# Amp_op4.net
KiCad netlist of a schematic drawn in Altium Designer
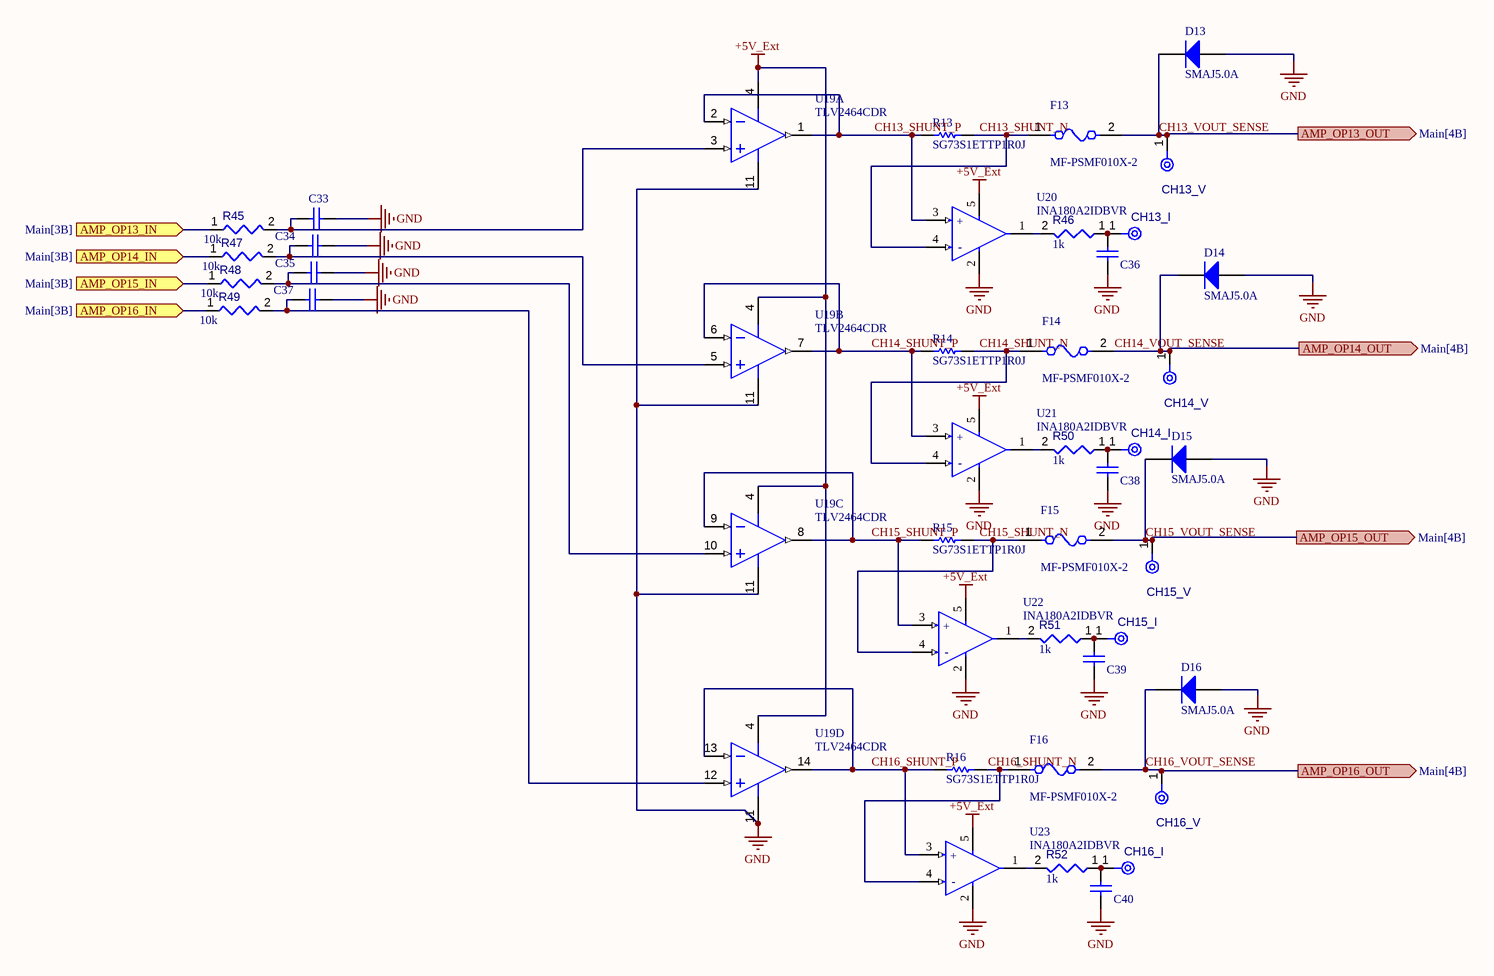
[diagram p0: Amp_op4.SchDoc]

(export (version "E")
  (design (tool "Eeschema 10.0.6"))
  (components
    (comp (ref "C33")
      (value "VJ0603Y104MXJCW1BC")
      (footprint "CAPC1608X95X40NL15T15")
      (fields (field (name "MANUFACTURER") "Vitramon"))
      (libsource (lib "Altium Content Vault") (part "CAP"))
    )
    (comp (ref "C34")
      (value "VJ0603Y104MXJCW1BC")
      (footprint "CAPC1608X95X40NL15T15")
      (fields (field (name "MANUFACTURER") "Vitramon"))
      (libsource (lib "Altium Content Vault") (part "CAP"))
    )
    (comp (ref "C35")
      (value "VJ0603Y104MXJCW1BC")
      (footprint "CAPC1608X95X40NL15T15")
      (fields (field (name "MANUFACTURER") "Vitramon"))
      (libsource (lib "Altium Content Vault") (part "CAP"))
    )
    (comp (ref "C36")
      (value "VJ0603Y104MXJCW1BC")
      (footprint "CAPC1608X95X40NL15T15")
      (fields (field (name "MANUFACTURER") "Vitramon"))
      (libsource (lib "Altium Content Vault") (part "CAP"))
    )
    (comp (ref "C37")
      (value "VJ0603Y104MXJCW1BC")
      (footprint "CAPC1608X95X40NL15T15")
      (fields (field (name "MANUFACTURER") "Vitramon"))
      (libsource (lib "Altium Content Vault") (part "CAP"))
    )
    (comp (ref "C38")
      (value "VJ0603Y104MXJCW1BC")
      (footprint "CAPC1608X95X40NL15T15")
      (fields (field (name "MANUFACTURER") "Vitramon"))
      (libsource (lib "Altium Content Vault") (part "CAP"))
    )
    (comp (ref "C39")
      (value "VJ0603Y104MXJCW1BC")
      (footprint "CAPC1608X95X40NL15T15")
      (fields (field (name "MANUFACTURER") "Vitramon"))
      (libsource (lib "Altium Content Vault") (part "CAP"))
    )
    (comp (ref "C40")
      (value "VJ0603Y104MXJCW1BC")
      (footprint "CAPC1608X95X40NL15T15")
      (fields (field (name "MANUFACTURER") "Vitramon"))
      (libsource (lib "Altium Content Vault") (part "CAP"))
    )
    (comp (ref "CH13_I")
      (value "TPAD6R")
      (footprint "TP06R")
      (description "0.6mm round")
      (libsource (lib "PCEIOT") (part "CMP-00028-00002-2"))
    )
    (comp (ref "CH13_V")
      (value "TPAD6R")
      (footprint "TP06R")
      (description "0.6mm round")
      (libsource (lib "PCEIOT") (part "CMP-00028-00002-2"))
    )
    (comp (ref "CH14_I")
      (value "TPAD6R")
      (footprint "TP06R")
      (description "0.6mm round")
      (libsource (lib "PCEIOT") (part "CMP-00028-00002-2"))
    )
    (comp (ref "CH14_V")
      (value "TPAD6R")
      (footprint "TP06R")
      (description "0.6mm round")
      (libsource (lib "PCEIOT") (part "CMP-00028-00002-2"))
    )
    (comp (ref "CH15_I")
      (value "TPAD6R")
      (footprint "TP06R")
      (description "0.6mm round")
      (libsource (lib "PCEIOT") (part "CMP-00028-00002-2"))
    )
    (comp (ref "CH15_V")
      (value "TPAD6R")
      (footprint "TP06R")
      (description "0.6mm round")
      (libsource (lib "PCEIOT") (part "CMP-00028-00002-2"))
    )
    (comp (ref "CH16_I")
      (value "TPAD6R")
      (footprint "TP06R")
      (description "0.6mm round")
      (libsource (lib "PCEIOT") (part "CMP-00028-00002-2"))
    )
    (comp (ref "CH16_V")
      (value "TPAD6R")
      (footprint "TP06R")
      (description "0.6mm round")
      (libsource (lib "PCEIOT") (part "CMP-00028-00002-2"))
    )
    (comp (ref "D13")
      (value "SMAJ5.0A")
      (footprint "BOUR-SMA-2_V")
      (fields (field (name "MANUFACTURER") "Bourns"))
      (libsource (lib "Altium Content Vault") (part "D-AK-2"))
    )
    (comp (ref "D14")
      (value "SMAJ5.0A")
      (footprint "BOUR-SMA-2_V")
      (fields (field (name "MANUFACTURER") "Bourns"))
      (libsource (lib "Altium Content Vault") (part "D-AK-2"))
    )
    (comp (ref "D15")
      (value "SMAJ5.0A")
      (footprint "BOUR-SMA-2_V")
      (fields (field (name "MANUFACTURER") "Bourns"))
      (libsource (lib "Altium Content Vault") (part "D-AK-2"))
    )
    (comp (ref "D16")
      (value "SMAJ5.0A")
      (footprint "BOUR-SMA-2_V")
      (fields (field (name "MANUFACTURER") "Bourns"))
      (libsource (lib "Altium Content Vault") (part "D-AK-2"))
    )
    (comp (ref "F13")
      (value "MF-PSMF010X-2")
      (footprint "FP-MF-PSMF-MFG")
      (description "PTC RESET FUSE 15V 100MA 0805")
      (fields
        (field (name "OCTOPART") "https://octopart.com/mf-psmf010x-2-bourns-7483441")
        (field (name "MANUFACTURER") "Bourns Inc.")
      )
      (libsource (lib "Altium Content Vault") (part "5bcf9b9f640e542cf0359d10258e979"))
    )
    (comp (ref "F14")
      (value "MF-PSMF010X-2")
      (footprint "FP-MF-PSMF-MFG")
      (description "PTC RESET FUSE 15V 100MA 0805")
      (fields
        (field (name "OCTOPART") "https://octopart.com/mf-psmf010x-2-bourns-7483441")
        (field (name "MANUFACTURER") "Bourns Inc.")
      )
      (libsource (lib "Altium Content Vault") (part "5bcf9b9f640e542cf0359d10258e979"))
    )
    (comp (ref "F15")
      (value "MF-PSMF010X-2")
      (footprint "FP-MF-PSMF-MFG")
      (description "PTC RESET FUSE 15V 100MA 0805")
      (fields
        (field (name "OCTOPART") "https://octopart.com/mf-psmf010x-2-bourns-7483441")
        (field (name "MANUFACTURER") "Bourns Inc.")
      )
      (libsource (lib "Altium Content Vault") (part "5bcf9b9f640e542cf0359d10258e979"))
    )
    (comp (ref "F16")
      (value "MF-PSMF010X-2")
      (footprint "FP-MF-PSMF-MFG")
      (description "PTC RESET FUSE 15V 100MA 0805")
      (fields
        (field (name "OCTOPART") "https://octopart.com/mf-psmf010x-2-bourns-7483441")
        (field (name "MANUFACTURER") "Bourns Inc.")
      )
      (libsource (lib "Altium Content Vault") (part "5bcf9b9f640e542cf0359d10258e979"))
    )
    (comp (ref "R13")
      (value "SG73S1ETTP1R0J")
      (footprint "RESC1005X40X25LL10T10")
      (fields (field (name "MANUFACTURER") "KOA Speer"))
      (libsource (lib "Altium Content Vault") (part "RES"))
    )
    (comp (ref "R14")
      (value "SG73S1ETTP1R0J")
      (footprint "RESC1005X40X25LL10T10")
      (fields (field (name "MANUFACTURER") "KOA Speer"))
      (libsource (lib "Altium Content Vault") (part "RES"))
    )
    (comp (ref "R15")
      (value "SG73S1ETTP1R0J")
      (footprint "RESC1005X40X25LL10T10")
      (fields (field (name "MANUFACTURER") "KOA Speer"))
      (libsource (lib "Altium Content Vault") (part "RES"))
    )
    (comp (ref "R16")
      (value "SG73S1ETTP1R0J")
      (footprint "RESC1005X40X25LL10T10")
      (fields (field (name "MANUFACTURER") "KOA Speer"))
      (libsource (lib "Altium Content Vault") (part "RES"))
    )
    (comp (ref "R45")
      (value "10k")
      (footprint "RESC0603(1608)_L")
      (description "Chip Resistor, 10 KOhm, +/- 1%, 01 W, -55 to 155 degC, 0603 (1608 Metric)")
      (fields (field (name "POWER") "100mW") (field (name "TOLERANCE") "1%"))
      (libsource (lib "PCEIOT") (part "CMP-009-00017-7"))
    )
    (comp (ref "R46")
      (value "1k")
      (footprint "RESC0603(1608)_L")
      (description "Chip Resistor, 1 KOhm, +/-1%, 0.1 W, -55 to 155 degC, 0603 (1608 Metric)")
      (fields (field (name "POWER") "100mW") (field (name "TOLERANCE") "1%"))
      (libsource (lib "PCEIOT") (part "CMP-009-00014-6"))
    )
    (comp (ref "R47")
      (value "10k")
      (footprint "RESC0603(1608)_L")
      (description "Chip Resistor, 10 KOhm, +/- 1%, 01 W, -55 to 155 degC, 0603 (1608 Metric)")
      (fields (field (name "POWER") "100mW") (field (name "TOLERANCE") "1%"))
      (libsource (lib "PCEIOT") (part "CMP-009-00017-7"))
    )
    (comp (ref "R48")
      (value "10k")
      (footprint "RESC0603(1608)_L")
      (description "Chip Resistor, 10 KOhm, +/- 1%, 01 W, -55 to 155 degC, 0603 (1608 Metric)")
      (fields (field (name "POWER") "100mW") (field (name "TOLERANCE") "1%"))
      (libsource (lib "PCEIOT") (part "CMP-009-00017-7"))
    )
    (comp (ref "R49")
      (value "10k")
      (footprint "RESC0603(1608)_L")
      (description "Chip Resistor, 10 KOhm, +/- 1%, 01 W, -55 to 155 degC, 0603 (1608 Metric)")
      (fields (field (name "POWER") "100mW") (field (name "TOLERANCE") "1%"))
      (libsource (lib "PCEIOT") (part "CMP-009-00017-7"))
    )
    (comp (ref "R50")
      (value "1k")
      (footprint "RESC0603(1608)_L")
      (description "Chip Resistor, 1 KOhm, +/-1%, 0.1 W, -55 to 155 degC, 0603 (1608 Metric)")
      (fields (field (name "POWER") "100mW") (field (name "TOLERANCE") "1%"))
      (libsource (lib "PCEIOT") (part "CMP-009-00014-6"))
    )
    (comp (ref "R51")
      (value "1k")
      (footprint "RESC0603(1608)_L")
      (description "Chip Resistor, 1 KOhm, +/-1%, 0.1 W, -55 to 155 degC, 0603 (1608 Metric)")
      (fields (field (name "POWER") "100mW") (field (name "TOLERANCE") "1%"))
      (libsource (lib "PCEIOT") (part "CMP-009-00014-6"))
    )
    (comp (ref "R52")
      (value "1k")
      (footprint "RESC0603(1608)_L")
      (description "Chip Resistor, 1 KOhm, +/-1%, 0.1 W, -55 to 155 degC, 0603 (1608 Metric)")
      (fields (field (name "POWER") "100mW") (field (name "TOLERANCE") "1%"))
      (libsource (lib "PCEIOT") (part "CMP-009-00014-6"))
    )
    (comp (ref "U19")
      (value "TLV2464CDR")
      (footprint "D0014A_N")
      (fields (field (name "MANUFACTURER") "Texas Instruments"))
      (libsource (lib "Altium Content Vault") (part "TI-TLV2464X-XX14"))
    )
    (comp (ref "U20")
      (value "INA180A2IDBVR")
      (footprint "FP-DBV0005A-MFG")
      (description "IC CURR SENSE 1 CIRCUIT SOT23-5")
      (libsource (lib "Altium Content Vault") (part "0a55cf1a948ad01a3239aec1b7efad0"))
    )
    (comp (ref "U21")
      (value "INA180A2IDBVR")
      (footprint "FP-DBV0005A-MFG")
      (description "IC CURR SENSE 1 CIRCUIT SOT23-5")
      (libsource (lib "Altium Content Vault") (part "0a55cf1a948ad01a3239aec1b7efad0"))
    )
    (comp (ref "U22")
      (value "INA180A2IDBVR")
      (footprint "FP-DBV0005A-MFG")
      (description "IC CURR SENSE 1 CIRCUIT SOT23-5")
      (libsource (lib "Altium Content Vault") (part "0a55cf1a948ad01a3239aec1b7efad0"))
    )
    (comp (ref "U23")
      (value "INA180A2IDBVR")
      (footprint "FP-DBV0005A-MFG")
      (description "IC CURR SENSE 1 CIRCUIT SOT23-5")
      (libsource (lib "Altium Content Vault") (part "0a55cf1a948ad01a3239aec1b7efad0"))
    )
  )
  (nets
    (net (code "1") (name "+5V_Ext") (class "Default")
      (node (ref "U19") (pin "4") (pinfunction "VDD+_4") (pintype "power_in"))
      (node (ref "U20") (pin "5") (pinfunction "VS_5") (pintype "power_in"))
      (node (ref "U21") (pin "5") (pinfunction "VS_5") (pintype "power_in"))
      (node (ref "U22") (pin "5") (pinfunction "VS_5") (pintype "power_in"))
      (node (ref "U23") (pin "5") (pinfunction "VS_5") (pintype "power_in"))
    )
    (net (code "2") (name "/AMP_OP13_IN") (class "Default")
      (node (ref "R45") (pin "1") (pinfunction "1_1") (pintype "passive"))
    )
    (net (code "3") (name "/AMP_OP14_IN") (class "Default")
      (node (ref "R47") (pin "1") (pinfunction "1_1") (pintype "passive"))
    )
    (net (code "4") (name "/AMP_OP15_IN") (class "Default")
      (node (ref "R48") (pin "1") (pinfunction "1_1") (pintype "passive"))
    )
    (net (code "5") (name "/AMP_OP16_IN") (class "Default")
      (node (ref "R49") (pin "1") (pinfunction "1_1") (pintype "passive"))
    )
    (net (code "6") (name "/CH13_SHUNT_N") (class "Default")
      (node (ref "F13") (pin "1") (pinfunction "1_1") (pintype "passive"))
      (node (ref "R13") (pin "2") (pinfunction "2_2") (pintype "passive"))
      (node (ref "U20") (pin "4") (pinfunction "IN-_4") (pintype "input"))
    )
    (net (code "7") (name "/CH13_SHUNT_P") (class "Default")
      (node (ref "R13") (pin "1") (pinfunction "1_1") (pintype "passive"))
      (node (ref "U19") (pin "1") (pinfunction "OUT1_1") (pintype "output"))
      (node (ref "U19") (pin "2") (pinfunction "IN1-_2") (pintype "input"))
      (node (ref "U20") (pin "3") (pinfunction "IN+_3") (pintype "input"))
    )
    (net (code "8") (name "/CH13_VOUT_SENSE") (class "Default")
      (node (ref "CH13_V") (pin "1") (pinfunction "TP_1") (pintype "passive"))
      (node (ref "D13") (pin "2") (pinfunction "K_2") (pintype "passive"))
      (node (ref "F13") (pin "2") (pinfunction "2_2") (pintype "passive"))
    )
    (net (code "9") (name "/CH14_SHUNT_N") (class "Default")
      (node (ref "F14") (pin "1") (pinfunction "1_1") (pintype "passive"))
      (node (ref "R14") (pin "2") (pinfunction "2_2") (pintype "passive"))
      (node (ref "U21") (pin "4") (pinfunction "IN-_4") (pintype "input"))
    )
    (net (code "10") (name "/CH14_SHUNT_P") (class "Default")
      (node (ref "R14") (pin "1") (pinfunction "1_1") (pintype "passive"))
      (node (ref "U19") (pin "6") (pinfunction "IN2-_6") (pintype "input"))
      (node (ref "U19") (pin "7") (pinfunction "OUT2_7") (pintype "output"))
      (node (ref "U21") (pin "3") (pinfunction "IN+_3") (pintype "input"))
    )
    (net (code "11") (name "/CH14_VOUT_SENSE") (class "Default")
      (node (ref "CH14_V") (pin "1") (pinfunction "TP_1") (pintype "passive"))
      (node (ref "D14") (pin "2") (pinfunction "K_2") (pintype "passive"))
      (node (ref "F14") (pin "2") (pinfunction "2_2") (pintype "passive"))
    )
    (net (code "12") (name "/CH15_SHUNT_N") (class "Default")
      (node (ref "F15") (pin "1") (pinfunction "1_1") (pintype "passive"))
      (node (ref "R15") (pin "2") (pinfunction "2_2") (pintype "passive"))
      (node (ref "U22") (pin "4") (pinfunction "IN-_4") (pintype "input"))
    )
    (net (code "13") (name "/CH15_SHUNT_P") (class "Default")
      (node (ref "R15") (pin "1") (pinfunction "1_1") (pintype "passive"))
      (node (ref "U19") (pin "8") (pinfunction "OUT3_8") (pintype "output"))
      (node (ref "U19") (pin "9") (pinfunction "IN3-_9") (pintype "input"))
      (node (ref "U22") (pin "3") (pinfunction "IN+_3") (pintype "input"))
    )
    (net (code "14") (name "/CH15_VOUT_SENSE") (class "Default")
      (node (ref "CH15_V") (pin "1") (pinfunction "TP_1") (pintype "passive"))
      (node (ref "D15") (pin "2") (pinfunction "K_2") (pintype "passive"))
      (node (ref "F15") (pin "2") (pinfunction "2_2") (pintype "passive"))
    )
    (net (code "15") (name "/CH16_SHUNT_N") (class "Default")
      (node (ref "F16") (pin "1") (pinfunction "1_1") (pintype "passive"))
      (node (ref "R16") (pin "2") (pinfunction "2_2") (pintype "passive"))
      (node (ref "U23") (pin "4") (pinfunction "IN-_4") (pintype "input"))
    )
    (net (code "16") (name "/CH16_SHUNT_P") (class "Default")
      (node (ref "R16") (pin "1") (pinfunction "1_1") (pintype "passive"))
      (node (ref "U19") (pin "13") (pinfunction "IN4-_13") (pintype "input"))
      (node (ref "U19") (pin "14") (pinfunction "OUT4_14") (pintype "output"))
      (node (ref "U23") (pin "3") (pinfunction "IN+_3") (pintype "input"))
    )
    (net (code "17") (name "/CH16_VOUT_SENSE") (class "Default")
      (node (ref "CH16_V") (pin "1") (pinfunction "TP_1") (pintype "passive"))
      (node (ref "D16") (pin "2") (pinfunction "K_2") (pintype "passive"))
      (node (ref "F16") (pin "2") (pinfunction "2_2") (pintype "passive"))
    )
    (net (code "18") (name "GND") (class "Default")
      (node (ref "C33") (pin "2") (pinfunction "2_2") (pintype "passive"))
      (node (ref "C34") (pin "2") (pinfunction "2_2") (pintype "passive"))
      (node (ref "C35") (pin "2") (pinfunction "2_2") (pintype "passive"))
      (node (ref "C36") (pin "2") (pinfunction "2_2") (pintype "passive"))
      (node (ref "C37") (pin "2") (pinfunction "2_2") (pintype "passive"))
      (node (ref "C38") (pin "2") (pinfunction "2_2") (pintype "passive"))
      (node (ref "C39") (pin "2") (pinfunction "2_2") (pintype "passive"))
      (node (ref "C40") (pin "2") (pinfunction "2_2") (pintype "passive"))
      (node (ref "D13") (pin "1") (pinfunction "A_1") (pintype "passive"))
      (node (ref "D14") (pin "1") (pinfunction "A_1") (pintype "passive"))
      (node (ref "D15") (pin "1") (pinfunction "A_1") (pintype "passive"))
      (node (ref "D16") (pin "1") (pinfunction "A_1") (pintype "passive"))
      (node (ref "U19") (pin "11") (pinfunction "GND_11") (pintype "power_in"))
      (node (ref "U20") (pin "2") (pinfunction "GND_2") (pintype "power_in"))
      (node (ref "U21") (pin "2") (pinfunction "GND_2") (pintype "power_in"))
      (node (ref "U22") (pin "2") (pinfunction "GND_2") (pintype "power_in"))
      (node (ref "U23") (pin "2") (pinfunction "GND_2") (pintype "power_in"))
    )
    (net (code "19") (name "Net-(CH13_I-TP)") (class "Default")
      (node (ref "C36") (pin "1") (pinfunction "1_1") (pintype "passive"))
      (node (ref "CH13_I") (pin "1") (pinfunction "TP_1") (pintype "passive"))
      (node (ref "R46") (pin "1") (pinfunction "1_1") (pintype "passive"))
    )
    (net (code "20") (name "Net-(CH14_I-TP)") (class "Default")
      (node (ref "C38") (pin "1") (pinfunction "1_1") (pintype "passive"))
      (node (ref "CH14_I") (pin "1") (pinfunction "TP_1") (pintype "passive"))
      (node (ref "R50") (pin "1") (pinfunction "1_1") (pintype "passive"))
    )
    (net (code "21") (name "Net-(CH15_I-TP)") (class "Default")
      (node (ref "C39") (pin "1") (pinfunction "1_1") (pintype "passive"))
      (node (ref "CH15_I") (pin "1") (pinfunction "TP_1") (pintype "passive"))
      (node (ref "R51") (pin "1") (pinfunction "1_1") (pintype "passive"))
    )
    (net (code "22") (name "Net-(CH16_I-TP)") (class "Default")
      (node (ref "C40") (pin "1") (pinfunction "1_1") (pintype "passive"))
      (node (ref "CH16_I") (pin "1") (pinfunction "TP_1") (pintype "passive"))
      (node (ref "R52") (pin "1") (pinfunction "1_1") (pintype "passive"))
    )
    (net (code "23") (name "Net-(U19A-IN1+)") (class "Default")
      (node (ref "C33") (pin "1") (pinfunction "1_1") (pintype "passive"))
      (node (ref "R45") (pin "2") (pinfunction "2_2") (pintype "passive"))
      (node (ref "U19") (pin "3") (pinfunction "IN1+_3") (pintype "input"))
    )
    (net (code "24") (name "Net-(U19B-IN2+)") (class "Default")
      (node (ref "C34") (pin "1") (pinfunction "1_1") (pintype "passive"))
      (node (ref "R47") (pin "2") (pinfunction "2_2") (pintype "passive"))
      (node (ref "U19") (pin "5") (pinfunction "IN2+_5") (pintype "input"))
    )
    (net (code "25") (name "Net-(U19C-IN3+)") (class "Default")
      (node (ref "C35") (pin "1") (pinfunction "1_1") (pintype "passive"))
      (node (ref "R48") (pin "2") (pinfunction "2_2") (pintype "passive"))
      (node (ref "U19") (pin "10") (pinfunction "IN3+_10") (pintype "input"))
    )
    (net (code "26") (name "Net-(U19D-IN4+)") (class "Default")
      (node (ref "C37") (pin "1") (pinfunction "1_1") (pintype "passive"))
      (node (ref "R49") (pin "2") (pinfunction "2_2") (pintype "passive"))
      (node (ref "U19") (pin "12") (pinfunction "IN4+_12") (pintype "input"))
    )
    (net (code "27") (name "Net-(U20-OUT)") (class "Default")
      (node (ref "R46") (pin "2") (pinfunction "2_2") (pintype "passive"))
      (node (ref "U20") (pin "1") (pinfunction "OUT_1") (pintype "passive"))
    )
    (net (code "28") (name "Net-(U21-OUT)") (class "Default")
      (node (ref "R50") (pin "2") (pinfunction "2_2") (pintype "passive"))
      (node (ref "U21") (pin "1") (pinfunction "OUT_1") (pintype "passive"))
    )
    (net (code "29") (name "Net-(U22-OUT)") (class "Default")
      (node (ref "R51") (pin "2") (pinfunction "2_2") (pintype "passive"))
      (node (ref "U22") (pin "1") (pinfunction "OUT_1") (pintype "passive"))
    )
    (net (code "30") (name "Net-(U23-OUT)") (class "Default")
      (node (ref "R52") (pin "2") (pinfunction "2_2") (pintype "passive"))
      (node (ref "U23") (pin "1") (pinfunction "OUT_1") (pintype "passive"))
    )
  )
)
